# pcb_business_card.net
KiCad netlist of a schematic drawn in EAGLE
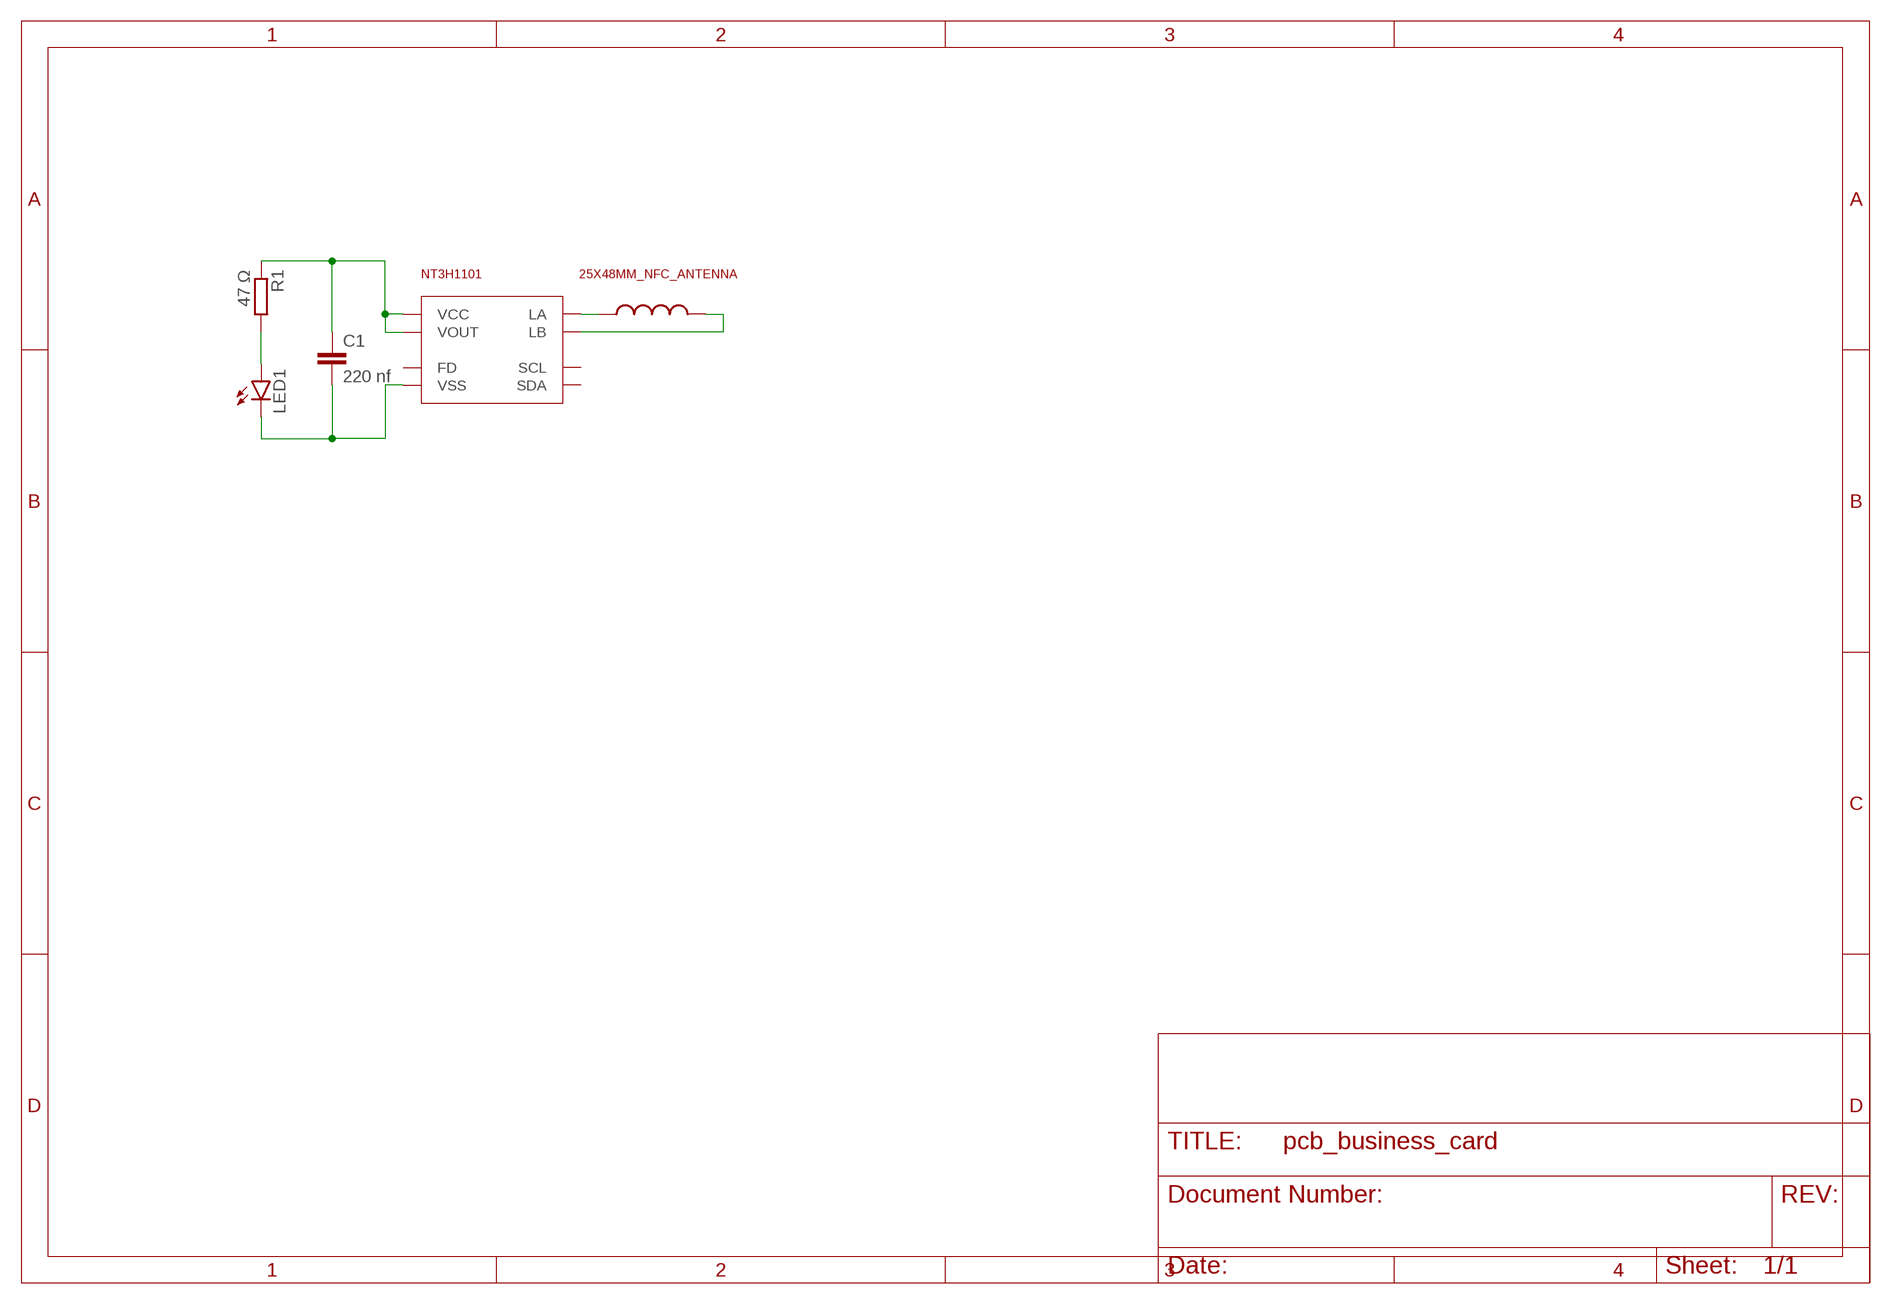
[diagram p0: schematic, sheet 1]

(export (version "E")
  (design (tool "Eeschema 10.0.6"))
  (components
    (comp (ref "ANT")
      (value "25X48MM_NFC_ANTENNA")
      (footprint "eagle-import:25X48MM_NFC")
      (libsource (lib "eagle-import") (part "25X48MM_NFC_ANTENNA"))
    )
    (comp (ref "C1")
      (value "220 nf")
      (footprint "eagle-import:C0603")
      (libsource (lib "eagle-import") (part "C-EUC0603"))
    )
    (comp (ref "LED1")
      (value "LEDCHIP-LED0805")
      (footprint "eagle-import:CHIP-LED0805")
      (libsource (lib "eagle-import") (part "LEDCHIP-LED0805"))
    )
    (comp (ref "NT3H1101")
      (value "NT3H")
      (footprint "eagle-import:XQFN8")
      (libsource (lib "eagle-import") (part "NT3H"))
    )
    (comp (ref "R1")
      (value "47 Ω")
      (footprint "eagle-import:R0603")
      (libsource (lib "eagle-import") (part "R-EU_R0603"))
    )
  )
  (nets
    (net (code "1") (name "Net-(ANT-PadP$1)") (class "Default")
      (node (ref "ANT") (pin "P$1") (pinfunction "P$1_P$1") (pintype "bidirectional"))
      (node (ref "NT3H1101") (pin "LB") (pinfunction "LB_LB") (pintype "bidirectional"))
    )
    (net (code "2") (name "Net-(ANT-PadP$2)") (class "Default")
      (node (ref "ANT") (pin "P$2") (pinfunction "P$2_P$2") (pintype "bidirectional"))
      (node (ref "NT3H1101") (pin "LA") (pinfunction "LA_LA") (pintype "bidirectional"))
    )
    (net (code "3") (name "Net-(C1-Pad1)") (class "Default")
      (node (ref "C1") (pin "1") (pinfunction "1_1") (pintype "passive"))
      (node (ref "NT3H1101") (pin "VCC") (pinfunction "VCC_VCC") (pintype "bidirectional"))
      (node (ref "NT3H1101") (pin "VOUT") (pinfunction "VOUT_VOUT") (pintype "bidirectional"))
      (node (ref "R1") (pin "1") (pinfunction "1_1") (pintype "passive"))
    )
    (net (code "4") (name "Net-(C1-Pad2)") (class "Default")
      (node (ref "C1") (pin "2") (pinfunction "2_2") (pintype "passive"))
      (node (ref "LED1") (pin "C") (pinfunction "C_C") (pintype "passive"))
      (node (ref "NT3H1101") (pin "VSS") (pinfunction "VSS_VSS") (pintype "bidirectional"))
    )
    (net (code "5") (name "Net-(LED1-PadA)") (class "Default")
      (node (ref "LED1") (pin "A") (pinfunction "A_A") (pintype "passive"))
      (node (ref "R1") (pin "2") (pinfunction "2_2") (pintype "passive"))
    )
    (net (code "6") (name "unconnected-(NT3H1101-PadFD)") (class "Default")
      (node (ref "NT3H1101") (pin "FD") (pinfunction "FD_FD") (pintype "bidirectional"))
    )
    (net (code "7") (name "unconnected-(NT3H1101-PadSCL)") (class "Default")
      (node (ref "NT3H1101") (pin "SCL") (pinfunction "SCL_SCL") (pintype "bidirectional"))
    )
    (net (code "8") (name "unconnected-(NT3H1101-PadSDA)") (class "Default")
      (node (ref "NT3H1101") (pin "SDA") (pinfunction "SDA_SDA") (pintype "bidirectional"))
    )
  )
)
